# 1_2V_regulator.net
KiCad netlist of a schematic drawn in Altium Designer
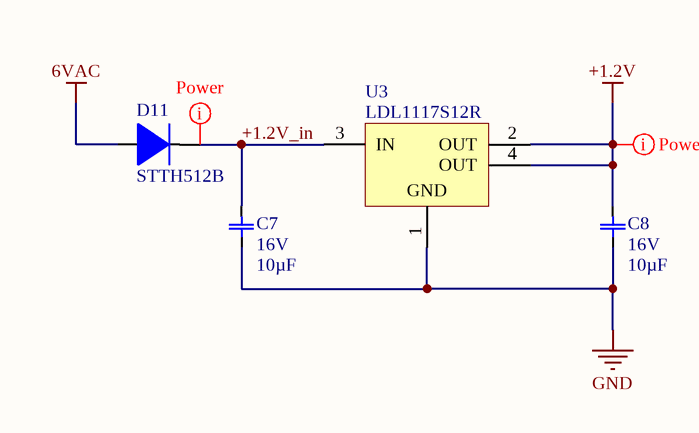
[diagram p0: 1.2V_regulator.SchDoc]

(export (version "E")
  (design (tool "Eeschema 10.0.6"))
  (components
    (comp (ref "C7")
      (value "10µF")
      (footprint "MLCC_1210")
      (description "MLCC 10µF 16V 1210")
      (fields (field (name "VOLTAGE") "16V"))
      (libsource (lib "Nixie") (part "MLCC 10µF 16V 1210"))
    )
    (comp (ref "C8")
      (value "10µF")
      (footprint "MLCC_1210")
      (description "MLCC 10µF 16V 1210")
      (fields (field (name "VOLTAGE") "16V"))
      (libsource (lib "Nixie") (part "MLCC 10µF 16V 1210"))
    )
    (comp (ref "D11")
      (value "STTH512B")
      (footprint "STTH512B")
      (description "Ultrafast recovery - 1200 V diode")
      (libsource (lib "Nixie") (part "STTH512B"))
    )
    (comp (ref "U3")
      (value "LDL1117S12R")
      (footprint "TLV1117")
      (description "Fixed LDO Voltage Regulator, 2.6 V to 18 V input, 170 mV Dropout, 1.2 V / 1.2 A out, SOT-223-4")
      (fields (field (name "MANUFACTURER") "Texas Instruments") (field (name "PARTNUMBER") "TLV1117LV30DCYT"))
      (libsource (lib "Nixie") (part "LDL1117S12R"))
    )
  )
  (nets
    (net (code "1") (name "+1.2V") (class "Default")
      (node (ref "C8") (pin "2") (pinfunction "2_2") (pintype "passive"))
      (node (ref "U3") (pin "2") (pinfunction "OUT_2") (pintype "power_in"))
      (node (ref "U3") (pin "4") (pinfunction "OUT_4") (pintype "power_in"))
    )
    (net (code "2") (name "/+1.2V_in") (class "Default")
      (node (ref "C7") (pin "2") (pinfunction "2_2") (pintype "passive"))
      (node (ref "D11") (pin "K") (pinfunction "K_K") (pintype "passive"))
      (node (ref "U3") (pin "3") (pinfunction "IN_3") (pintype "power_in"))
    )
    (net (code "3") (name "6VAC") (class "Default")
      (node (ref "D11") (pin "A") (pinfunction "A_A") (pintype "passive"))
    )
    (net (code "4") (name "GND") (class "Default")
      (node (ref "C7") (pin "1") (pinfunction "1_1") (pintype "passive"))
      (node (ref "C8") (pin "1") (pinfunction "1_1") (pintype "passive"))
      (node (ref "U3") (pin "1") (pinfunction "GND_1") (pintype "power_in"))
    )
  )
)
